# relay_switch.net
KiCad netlist of a schematic drawn in EAGLE
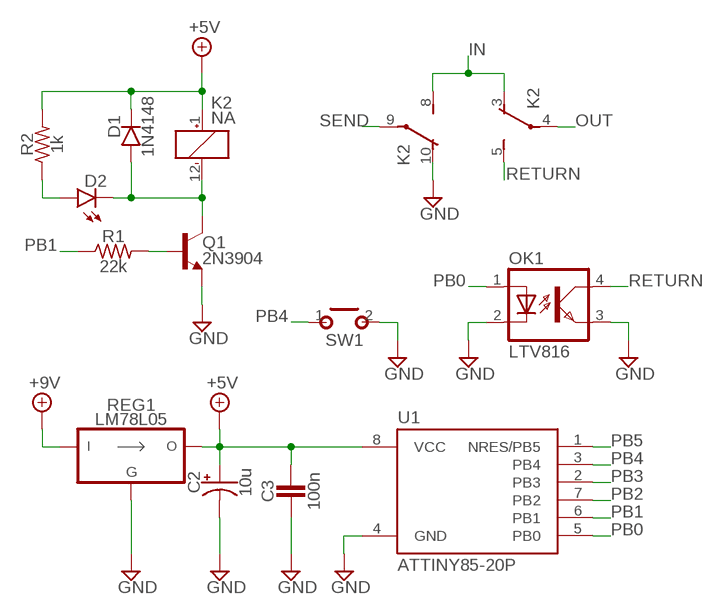
[diagram p0: schematic, sheet 1]

(export (version "E")
  (design (tool "Eeschema 10.0.6"))
  (components
    (comp (ref "C2")
      (value "10u")
      (footprint "eagle-import:050_020")
      (libsource (lib "eagle-import") (part "0500"))
    )
    (comp (ref "C3")
      (value "100n")
      (footprint "eagle-import:050X030_025_2")
      (libsource (lib "eagle-import") (part "CER/FILM2"))
    )
    (comp (ref "D1")
      (value "1N4148")
      (footprint "eagle-import:DO35-2")
      (libsource (lib "eagle-import") (part "DO35.2"))
    )
    (comp (ref "D2")
      (value "LED")
      (footprint "eagle-import:3MM_D")
      (libsource (lib "eagle-import") (part "LED"))
    )
    (comp (ref "K2") (value "NA") (footprint "eagle-import:NA") (libsource (lib "eagle-import") (part "NA")))
    (comp (ref "OK1")
      (value "LTV816")
      (footprint "eagle-import:DIL04")
      (libsource (lib "eagle-import") (part "LTV816"))
    )
    (comp (ref "Q1")
      (value "2N3904")
      (footprint "eagle-import:TO92-")
      (libsource (lib "eagle-import") (part "2N3904"))
    )
    (comp (ref "R1")
      (value "22k")
      (footprint "eagle-import:R0207_3")
      (libsource (lib "eagle-import") (part "R_.3B"))
    )
    (comp (ref "R2")
      (value "1k")
      (footprint "eagle-import:R0207_3")
      (libsource (lib "eagle-import") (part "R_.3B"))
    )
    (comp (ref "REG1")
      (value "LM78L05")
      (footprint "eagle-import:TO92-")
      (libsource (lib "eagle-import") (part "LM78L05"))
    )
    (comp (ref "SW1")
      (value "MOMENTARY")
      (footprint "eagle-import:SPST")
      (libsource (lib "eagle-import") (part "MOMENTARY"))
    )
    (comp (ref "U1")
      (value "ATTINY85-20P")
      (footprint "eagle-import:PDIP08_300MIL")
      (libsource (lib "eagle-import") (part "ATTINY85P-20"))
    )
  )
  (nets
    (net (code "1") (name "+5V") (class "Default")
      (node (ref "C2") (pin "+") (pinfunction "+_+") (pintype "passive"))
      (node (ref "C3") (pin "1") (pinfunction "1_1") (pintype "passive"))
      (node (ref "D1") (pin "C") (pinfunction "C_C") (pintype "passive"))
      (node (ref "K2") (pin "1") (pinfunction "+_1") (pintype "passive"))
      (node (ref "R2") (pin "2") (pinfunction "2_2") (pintype "passive"))
      (node (ref "REG1") (pin "3") (pinfunction "VO_3") (pintype "passive"))
      (node (ref "U1") (pin "8") (pinfunction "VCC_8") (pintype "power_in"))
    )
    (net (code "2") (name "+9V") (class "Default")
      (node (ref "REG1") (pin "1") (pinfunction "VI_1") (pintype "input"))
    )
    (net (code "3") (name "/IN") (class "Default")
      (node (ref "K2") (pin "3") (pinfunction "O_3") (pintype "passive"))
      (node (ref "K2") (pin "8") (pinfunction "S_8") (pintype "passive"))
    )
    (net (code "4") (name "/OUT") (class "Default")
      (node (ref "K2") (pin "4") (pinfunction "P_4") (pintype "passive"))
    )
    (net (code "5") (name "/PB0") (class "Default")
      (node (ref "OK1") (pin "1") (pinfunction "A_1") (pintype "passive"))
      (node (ref "U1") (pin "5") (pinfunction "PB0_5") (pintype "bidirectional"))
    )
    (net (code "6") (name "/PB1") (class "Default")
      (node (ref "R1") (pin "1") (pinfunction "1_1") (pintype "passive"))
      (node (ref "U1") (pin "6") (pinfunction "PB1_6") (pintype "bidirectional"))
    )
    (net (code "7") (name "/PB2") (class "Default")
      (node (ref "U1") (pin "7") (pinfunction "PB2_7") (pintype "bidirectional"))
    )
    (net (code "8") (name "/PB3") (class "Default")
      (node (ref "U1") (pin "2") (pinfunction "PB3_2") (pintype "bidirectional"))
    )
    (net (code "9") (name "/PB4") (class "Default")
      (node (ref "SW1") (pin "1") (pinfunction "P_1") (pintype "passive"))
      (node (ref "U1") (pin "3") (pinfunction "PB4_3") (pintype "bidirectional"))
    )
    (net (code "10") (name "/PB5") (class "Default")
      (node (ref "U1") (pin "1") (pinfunction "NRES/PB5_1") (pintype "bidirectional"))
    )
    (net (code "11") (name "/RETURN") (class "Default")
      (node (ref "K2") (pin "5") (pinfunction "S_5") (pintype "passive"))
      (node (ref "OK1") (pin "4") (pinfunction "COL_4") (pintype "passive"))
    )
    (net (code "12") (name "/SEND") (class "Default")
      (node (ref "K2") (pin "9") (pinfunction "P_9") (pintype "passive"))
    )
    (net (code "13") (name "GND") (class "Default")
      (node (ref "C2") (pin "-") (pinfunction "-_-") (pintype "passive"))
      (node (ref "C3") (pin "2") (pinfunction "2_2") (pintype "passive"))
      (node (ref "K2") (pin "10") (pinfunction "O_10") (pintype "passive"))
      (node (ref "OK1") (pin "2") (pinfunction "C_2") (pintype "passive"))
      (node (ref "OK1") (pin "3") (pinfunction "EMIT_3") (pintype "passive"))
      (node (ref "Q1") (pin "3") (pinfunction "E_3") (pintype "passive"))
      (node (ref "REG1") (pin "2") (pinfunction "GND_2") (pintype "passive"))
      (node (ref "SW1") (pin "2") (pinfunction "S_2") (pintype "passive"))
      (node (ref "U1") (pin "4") (pinfunction "GND_4") (pintype "power_in"))
    )
    (net (code "14") (name "Net-(D2-A)") (class "Default")
      (node (ref "D2") (pin "ANODE") (pinfunction "A_ANODE") (pintype "passive"))
      (node (ref "R2") (pin "1") (pinfunction "1_1") (pintype "passive"))
    )
    (net (code "15") (name "Net-(D2-C)") (class "Default")
      (node (ref "D1") (pin "A") (pinfunction "A_A") (pintype "passive"))
      (node (ref "D2") (pin "P$1") (pinfunction "C_P$1") (pintype "passive"))
      (node (ref "K2") (pin "12") (pinfunction "-_12") (pintype "passive"))
      (node (ref "Q1") (pin "1") (pinfunction "C_1") (pintype "passive"))
    )
    (net (code "16") (name "Net-(Q1-B)") (class "Default")
      (node (ref "Q1") (pin "2") (pinfunction "B_2") (pintype "passive"))
      (node (ref "R1") (pin "2") (pinfunction "2_2") (pintype "passive"))
    )
  )
)
